# power_24V.net
KiCad netlist of a schematic drawn in Altium Designer
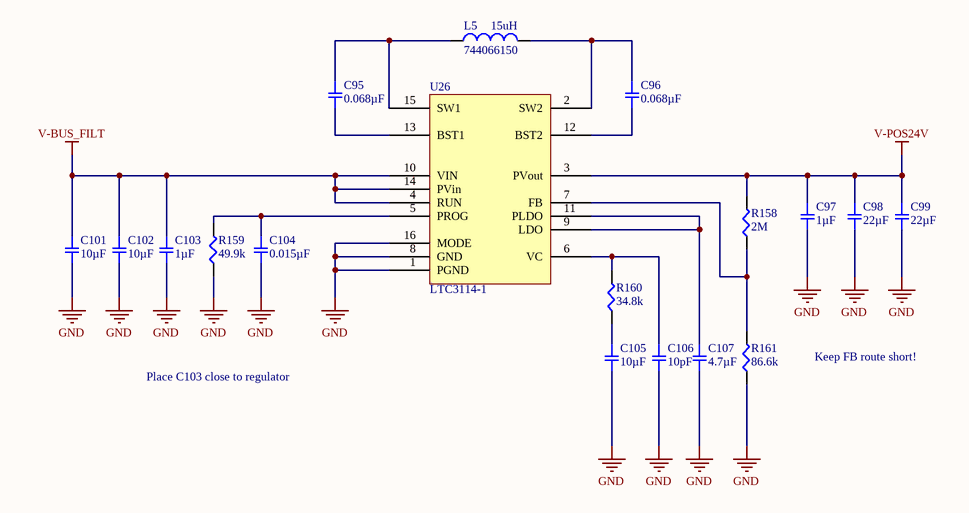
[diagram p0: power_24V.SchDoc]

(export (version "E")
  (design (tool "Eeschema 10.0.6"))
  (components
    (comp (ref "C95")
      (value "0.068µF")
      (footprint "SMD-0805C")
      (description "CAP CER 0.068UF 50V X7R 0805")
      (fields
        (field (name "DIGI-KEY PART NUMBER") "490-5807-1-ND")
        (field (name "PART NUMBER") "GCJ21BR71H683KA01L")
      )
      (libsource (lib "capacitors") (part "GCJ21BR71H683KA01L"))
    )
    (comp (ref "C96")
      (value "0.068µF")
      (footprint "SMD-0805C")
      (description "CAP CER 0.068UF 50V X7R 0805")
      (fields
        (field (name "DIGI-KEY PART NUMBER") "490-5807-1-ND")
        (field (name "PART NUMBER") "GCJ21BR71H683KA01L")
      )
      (libsource (lib "capacitors") (part "GCJ21BR71H683KA01L"))
    )
    (comp (ref "C97")
      (value "1µF")
      (footprint "SMD-0805C")
      (description "CAP CER 1UF 50V X7R 0805")
      (fields
        (field (name "DIGI-KEY PART NUMBER") "490-10667-1-ND")
        (field (name "PART NUMBER") "GCJ21BR71H105KA01L")
      )
      (libsource (lib "capacitors") (part "GCJ21BR71H105KA01L"))
    )
    (comp (ref "C98")
      (value "22µF")
      (footprint "SMD-1206C")
      (description "CAP CER 22UF 25V X5R 1206")
      (fields
        (field (name "DIGI-KEY PART NUMBER") "490-5527-1-ND")
        (field (name "PART NUMBER") "GRM31CR61E226KE15L")
      )
      (libsource (lib "capacitors") (part "GRM31CR61E226KE15L"))
    )
    (comp (ref "C99")
      (value "22µF")
      (footprint "SMD-1206C")
      (description "CAP CER 22UF 25V X5R 1206")
      (fields
        (field (name "DIGI-KEY PART NUMBER") "490-5527-1-ND")
        (field (name "PART NUMBER") "GRM31CR61E226KE15L")
      )
      (libsource (lib "capacitors") (part "GRM31CR61E226KE15L"))
    )
    (comp (ref "C101")
      (value "10µF")
      (footprint "SMD-1206C")
      (description "CAP CER 10UF 50V X5R 1206")
      (fields
        (field (name "DIGI-KEY PART NUMBER") "490-5961-1-ND")
        (field (name "PART NUMBER") "GRM31CR61H106KA12L")
      )
      (libsource (lib "capacitors") (part "GRM31CR61H106KA12L"))
    )
    (comp (ref "C102")
      (value "10µF")
      (footprint "SMD-1206C")
      (description "CAP CER 10UF 50V X5R 1206")
      (fields
        (field (name "DIGI-KEY PART NUMBER") "490-5961-1-ND")
        (field (name "PART NUMBER") "GRM31CR61H106KA12L")
      )
      (libsource (lib "capacitors") (part "GRM31CR61H106KA12L"))
    )
    (comp (ref "C103")
      (value "1µF")
      (footprint "SMD-1206C")
      (description "CAP CER 1UF 50V X7R 1206")
      (fields
        (field (name "DIGI-KEY PART NUMBER") "490-5810-1-ND")
        (field (name "PART NUMBER") "GCJ31MR71H105KA12L")
      )
      (libsource (lib "capacitors") (part "GCJ31MR71H105KA12L"))
    )
    (comp (ref "C104")
      (value "0.015µF")
      (footprint "SMD-0805C")
      (description "CAP CER 0.015UF 250V X7T 0805")
      (fields
        (field (name "DIGI-KEY PART NUMBER") "490-13987-1-ND")
        (field (name "PART NUMBER") "GC321AD72E153KX01D")
      )
      (libsource (lib "capacitors") (part "GC321AD72E153KX01D"))
    )
    (comp (ref "C105")
      (value "10µF")
      (footprint "SMD-1206C")
      (description "CAP CER 10UF 50V X5R 1206")
      (fields
        (field (name "DIGI-KEY PART NUMBER") "490-5961-1-ND")
        (field (name "PART NUMBER") "GRM31CR61H106KA12L")
      )
      (libsource (lib "capacitors") (part "GRM31CR61H106KA12L"))
    )
    (comp (ref "C106")
      (value "10pF")
      (footprint "SMD-0805C")
      (description "CAP CER 10PF 100V NP0 0805")
      (fields
        (field (name "DIGI-KEY PART NUMBER") "490-6098-1-ND")
        (field (name "PART NUMBER") "GQM2195C2A100GB01D")
      )
      (libsource (lib "capacitors") (part "GQM2195C2A100GB01D"))
    )
    (comp (ref "C107")
      (value "4.7µF")
      (footprint "SMD-1206C")
      (description "CAP CER 4.7UF 50V X7S 1206")
      (fields
        (field (name "DIGI-KEY PART NUMBER") "490-11167-1-ND")
        (field (name "PART NUMBER") "GCM31CC71H475KA03L")
      )
      (libsource (lib "capacitors") (part "GCM31CC71H475KA03L"))
    )
    (comp (ref "L5")
      (value "744066150")
      (footprint "INDP100100X38N")
      (description "FIXED IND 15UH 3.2A 50 MOHM SMD")
      (fields
        (field (name "MANUFACTURER") "Wurth Electronics")
        (field (name "TOLERANCE") "30%")
        (field (name "INDUCTANCE") "15uH")
      )
      (libsource (lib "inductor") (part "744066150"))
    )
    (comp (ref "R158")
      (value "2M")
      (footprint "SMD-0805-RES")
      (description "RES SMD 2M OHM 1% 1/8W 0805")
      (fields
        (field (name "PART NUMBER") "ERJ-6ENF2004V")
        (field (name "DIGI-KEY PART NUMBER") "P2.00MCCT-ND")
      )
      (libsource (lib "resistors") (part "ERJ-6ENF2004V"))
    )
    (comp (ref "R159")
      (value "49.9k")
      (footprint "SMD-0805-RES")
      (description "RES SMD 49.9K OHM 1% 1/8W 0805")
      (fields
        (field (name "PART NUMBER") "ERJ-6ENF4992V")
        (field (name "DIGI-KEY PART NUMBER") "P49.9KCCT-ND")
      )
      (libsource (lib "resistors") (part "ERJ-6ENF4992V"))
    )
    (comp (ref "R160")
      (value "34.8k")
      (footprint "SMD-0805-RES")
      (description "RES SMD 34.8K OHM 1% 1/8W 0805")
      (fields
        (field (name "PART NUMBER") "ERJ-6ENF3482V")
        (field (name "DIGI-KEY PART NUMBER") "P34.8KCCT-ND")
      )
      (libsource (lib "resistors") (part "ERJ-6ENF3482V"))
    )
    (comp (ref "R161")
      (value "86.6k")
      (footprint "SMD-0805-RES")
      (description "RES SMD 86.6K OHM 1% 1/8W 0805")
      (fields
        (field (name "PART NUMBER") "ERJ-6ENF8662V")
        (field (name "DIGI-KEY PART NUMBER") "P86.6KCCT-ND")
      )
      (libsource (lib "resistors") (part "ERJ-6ENF8662V"))
    )
    (comp (ref "U26")
      (value "LTC3114-1")
      (footprint "TSOP65P640X110_HS-17N")
      (fields
        (field (name "MANUFACTURER") "Analog Devices / Linear Technology")
        (field (name "MANUFACTURER PART NUMBER") "LTC3114EFE-1#TRPBF")
      )
      (libsource (lib "ic") (part "LTC3114-1"))
    )
  )
  (nets
    (net (code "1") (name "GND") (class "Default")
      (node (ref "C101") (pin "2") (pinfunction "2_2") (pintype "passive"))
      (node (ref "C102") (pin "2") (pinfunction "2_2") (pintype "passive"))
      (node (ref "C103") (pin "2") (pinfunction "2_2") (pintype "passive"))
      (node (ref "C104") (pin "2") (pinfunction "2_2") (pintype "passive"))
      (node (ref "C105") (pin "2") (pinfunction "2_2") (pintype "passive"))
      (node (ref "C106") (pin "2") (pinfunction "2_2") (pintype "passive"))
      (node (ref "C107") (pin "2") (pinfunction "2_2") (pintype "passive"))
      (node (ref "C97") (pin "2") (pinfunction "2_2") (pintype "passive"))
      (node (ref "C98") (pin "2") (pinfunction "2_2") (pintype "passive"))
      (node (ref "C99") (pin "2") (pinfunction "2_2") (pintype "passive"))
      (node (ref "R159") (pin "1") (pinfunction "1_1") (pintype "passive"))
      (node (ref "R161") (pin "1") (pinfunction "1_1") (pintype "passive"))
      (node (ref "U26") (pin "1") (pinfunction "PGND_1") (pintype "passive"))
      (node (ref "U26") (pin "16") (pinfunction "MODE_16") (pintype "passive"))
      (node (ref "U26") (pin "8") (pinfunction "GND_8") (pintype "passive"))
    )
    (net (code "2") (name "Net-(C105-Pad1)") (class "Default")
      (node (ref "C105") (pin "1") (pinfunction "1_1") (pintype "passive"))
      (node (ref "R160") (pin "1") (pinfunction "1_1") (pintype "passive"))
    )
    (net (code "3") (name "Net-(U26-BST1)") (class "Default")
      (node (ref "C95") (pin "2") (pinfunction "2_2") (pintype "passive"))
      (node (ref "U26") (pin "13") (pinfunction "BST1_13") (pintype "passive"))
    )
    (net (code "4") (name "Net-(U26-BST2)") (class "Default")
      (node (ref "C96") (pin "2") (pinfunction "2_2") (pintype "passive"))
      (node (ref "U26") (pin "12") (pinfunction "BST2_12") (pintype "passive"))
    )
    (net (code "5") (name "Net-(U26-FB)") (class "Default")
      (node (ref "R158") (pin "1") (pinfunction "1_1") (pintype "passive"))
      (node (ref "R161") (pin "2") (pinfunction "2_2") (pintype "passive"))
      (node (ref "U26") (pin "7") (pinfunction "FB_7") (pintype "passive"))
    )
    (net (code "6") (name "Net-(U26-LDO)") (class "Default")
      (node (ref "C107") (pin "1") (pinfunction "1_1") (pintype "passive"))
      (node (ref "U26") (pin "11") (pinfunction "PLDO_11") (pintype "passive"))
      (node (ref "U26") (pin "9") (pinfunction "LDO_9") (pintype "passive"))
    )
    (net (code "7") (name "Net-(U26-PROG)") (class "Default")
      (node (ref "C104") (pin "1") (pinfunction "1_1") (pintype "passive"))
      (node (ref "R159") (pin "2") (pinfunction "2_2") (pintype "passive"))
      (node (ref "U26") (pin "5") (pinfunction "PROG_5") (pintype "passive"))
    )
    (net (code "8") (name "Net-(U26-SW1)") (class "Default")
      (node (ref "C95") (pin "1") (pinfunction "1_1") (pintype "passive"))
      (node (ref "L5") (pin "1") (pinfunction "1_1") (pintype "passive"))
      (node (ref "U26") (pin "15") (pinfunction "SW1_15") (pintype "passive"))
    )
    (net (code "9") (name "Net-(U26-SW2)") (class "Default")
      (node (ref "C96") (pin "1") (pinfunction "1_1") (pintype "passive"))
      (node (ref "L5") (pin "2") (pinfunction "2_2") (pintype "passive"))
      (node (ref "U26") (pin "2") (pinfunction "SW2_2") (pintype "passive"))
    )
    (net (code "10") (name "Net-(U26-VC)") (class "Default")
      (node (ref "C106") (pin "1") (pinfunction "1_1") (pintype "passive"))
      (node (ref "R160") (pin "2") (pinfunction "2_2") (pintype "passive"))
      (node (ref "U26") (pin "6") (pinfunction "VC_6") (pintype "passive"))
    )
    (net (code "11") (name "V-BUS_FILT") (class "Default")
      (node (ref "C101") (pin "1") (pinfunction "1_1") (pintype "passive"))
      (node (ref "C102") (pin "1") (pinfunction "1_1") (pintype "passive"))
      (node (ref "C103") (pin "1") (pinfunction "1_1") (pintype "passive"))
      (node (ref "U26") (pin "10") (pinfunction "VIN_10") (pintype "passive"))
      (node (ref "U26") (pin "14") (pinfunction "PVin_14") (pintype "passive"))
      (node (ref "U26") (pin "4") (pinfunction "RUN_4") (pintype "passive"))
    )
    (net (code "12") (name "V-POS24V") (class "Default")
      (node (ref "C97") (pin "1") (pinfunction "1_1") (pintype "passive"))
      (node (ref "C98") (pin "1") (pinfunction "1_1") (pintype "passive"))
      (node (ref "C99") (pin "1") (pinfunction "1_1") (pintype "passive"))
      (node (ref "R158") (pin "2") (pinfunction "2_2") (pintype "passive"))
      (node (ref "U26") (pin "3") (pinfunction "PVout_3") (pintype "passive"))
    )
  )
)
